# 04_-_3_5_inch.net
KiCad netlist of a schematic drawn in Altium Designer
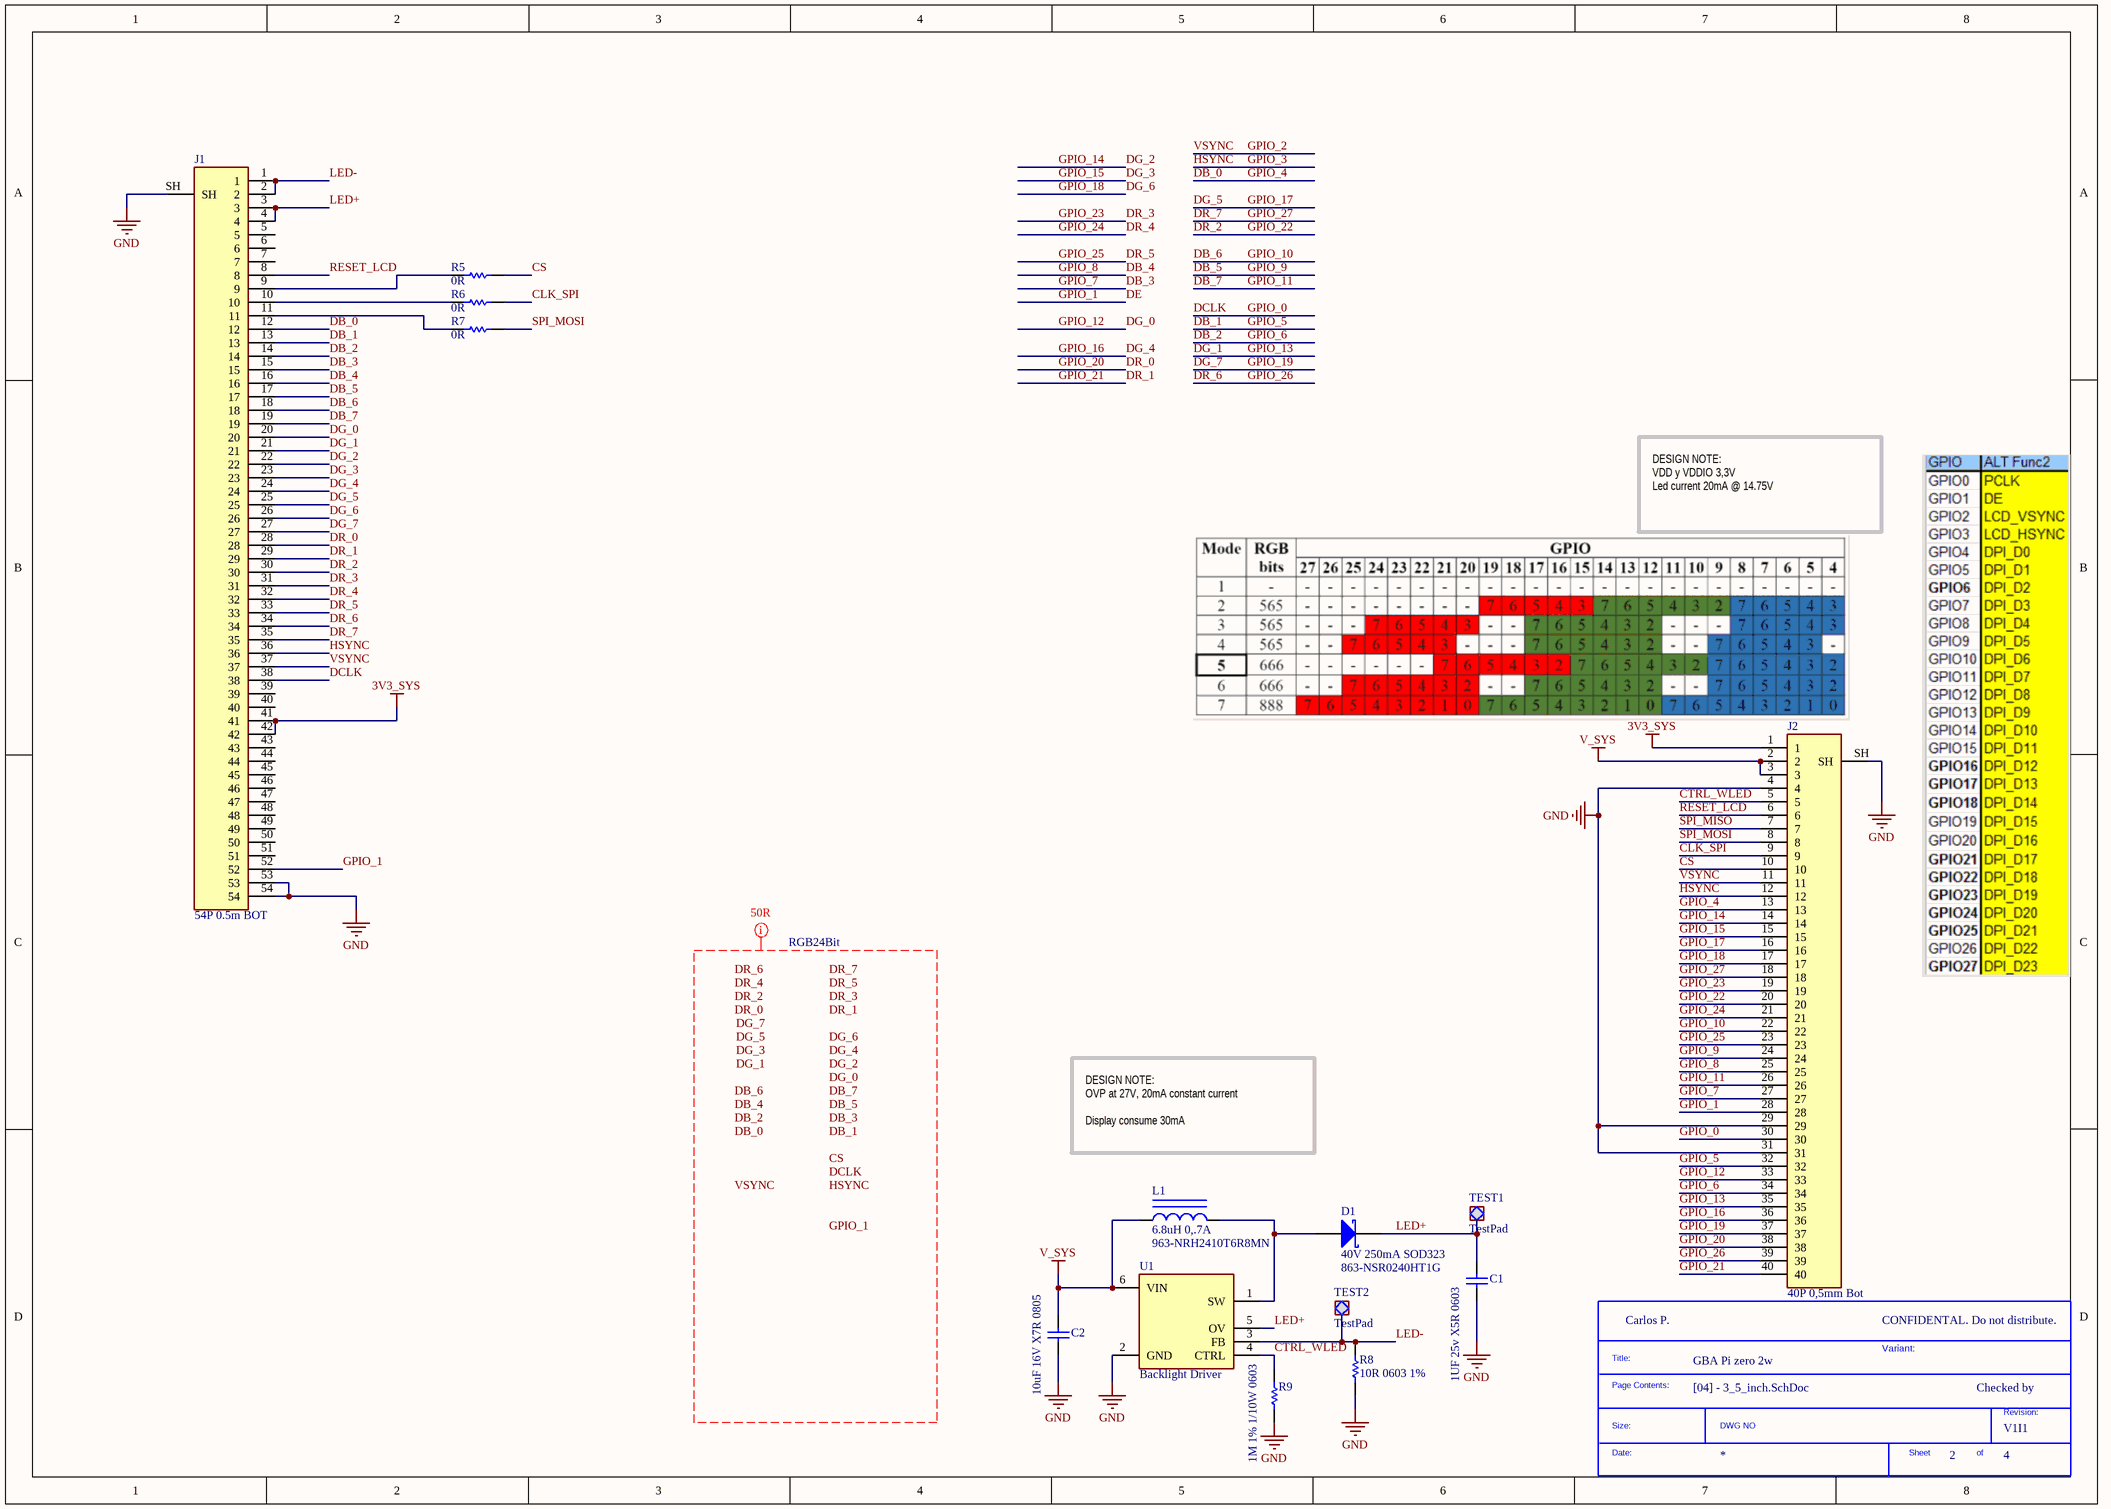
[diagram p0: [04] - 3_5_inch.SchDoc]

(export (version "E")
  (design (tool "Eeschema 10.0.6"))
  (components
    (comp (ref "C1")
      (value "1UF 25v X5R 0603")
      (footprint "C 0603/1608")
      (description "CAP CER 1UF 25V X5R 0603")
      (fields
        (field (name "MANUFACTURER") "Yageo")
        (field (name "MANUFACTURER PART NUMBER") "CC0603KRX5R8BB105")
      )
      (libsource (lib "CM3Board_V1I2") (part "CC0603KRX5R8BB105"))
    )
    (comp (ref "C2")
      (value "10uF 16V X7R 0805")
      (footprint "C 0805/2012")
      (description "CAP CER 10UF 16V X7R 0805")
      (fields
        (field (name "MANUFACTURER") "Samsung Electro-Mechanics")
        (field (name "MANUFACTURER PART NUMBER") "CL21B106KOQNNNE")
      )
      (libsource (lib "CM3Board_V1I2") (part "CL21B106KOQNNNE"))
    )
    (comp (ref "D1")
      (value "40V 250mA SOD323")
      (footprint "SOD-323")
      (description "DIODE SCHOTTKY 40V 250MA SOD323")
      (fields
        (field (name "MANUFACTURER") "ON Semiconductor")
        (field (name "MANUFACTURER PART NUMBER") "NSR0240HT1G")
        (field (name "SUPPLIER PART NUMBER 1") "863-NSR0240HT1G")
      )
      (libsource (lib "DPI_LVDS") (part "NSR0240HT1G"))
    )
    (comp (ref "J1")
      (value "54P 0.5m BOT")
      (footprint "FFC2B35-54-G")
      (description "54W, 0.5MM Ffc Con, R/a, Bottom Con")
      (fields
        (field (name "MANUFACTURER") "Global Connector Technology")
        (field (name "MANUFACTURER PART NUMBER") "FFC2B35-54-G")
      )
      (libsource (lib "GBA") (part "FFC2B35-54-G"))
    )
    (comp (ref "J2")
      (value "40P 0,5mm Bot")
      (footprint "417345920")
      (description "CONN FPC BOTTOM 40POS 0.50MM R/A")
      (fields
        (field (name "MANUFACTURER") "TE Connectivity")
        (field (name "MANUFACTURER PART NUMBER") "4-1734592-0")
      )
      (libsource (lib "GBA") (part "4-1734592-0"))
    )
    (comp (ref "L1")
      (value "6.8uH 0,.7A")
      (footprint "NRH2410T6R8MN")
      (description "Inductor Power Shielded Wirewound 6.8uH 20% 100KHz Ferrite 0.57A 0.492Ohm DCR T/R")
      (fields
        (field (name "MANUFACTURER") "Taiyo Yuden")
        (field (name "MANUFACTURER PART NUMBER") "NRH2410T6R8MN")
        (field (name "SUPPLIER PART NUMBER 1") "963-NRH2410T6R8MN")
      )
      (libsource (lib "GBA") (part "NRH2410T6R8MN"))
    )
    (comp (ref "R5")
      (value "0R")
      (footprint "R 0603/1608")
      (description "RES SMD 0 OHM JUMPER 1/10W 0603")
      (fields
        (field (name "MANUFACTURER") "Yageo")
        (field (name "MANUFACTURER PART NUMBER") "RC0603JR-070RL")
      )
      (libsource (lib "CM3Board_V1I2") (part "RC0603JR-070RL"))
    )
    (comp (ref "R6")
      (value "0R")
      (footprint "R 0603/1608")
      (description "RES SMD 0 OHM JUMPER 1/10W 0603")
      (fields
        (field (name "MANUFACTURER") "Yageo")
        (field (name "MANUFACTURER PART NUMBER") "RC0603JR-070RL")
      )
      (libsource (lib "CM3Board_V1I2") (part "RC0603JR-070RL"))
    )
    (comp (ref "R7")
      (value "0R")
      (footprint "R 0603/1608")
      (description "RES SMD 0 OHM JUMPER 1/10W 0603")
      (fields
        (field (name "MANUFACTURER") "Yageo")
        (field (name "MANUFACTURER PART NUMBER") "RC0603JR-070RL")
      )
      (libsource (lib "CM3Board_V1I2") (part "RC0603JR-070RL"))
    )
    (comp (ref "R8")
      (value "10R 0603 1%")
      (footprint "R 0603/1608")
      (description "High Precision-High Stability Chip Resistor Thin Film 0603 10Ohm 1% Paper T/R")
      (fields
        (field (name "MANUFACTURER") "Yageo")
        (field (name "MANUFACTURER PART NUMBER") "RT0603FRE0710RL")
      )
      (libsource (lib "GBA") (part "RT0603FRE0710RL"))
    )
    (comp (ref "R9")
      (value "1M 1% 1/10W 0603")
      (footprint "R 0603/1608")
      (description "RES SMD 1M OHM 1% 1/10W 0603")
      (fields (field (name "TOLERANCE") "1%"))
      (libsource (lib "CM3Board_V1I2") (part "RC0603FR-071ML"))
    )
    (comp (ref "TEST1")
      (value "TestPad")
      (footprint "TestPad")
      (description "Probe Pad, SMT, ROUND, 2.0MM")
      (libsource (lib "CM3Board") (part "PP_SMT_ROUND_2MM"))
    )
    (comp (ref "TEST2")
      (value "TestPad")
      (footprint "TestPad")
      (description "Probe Pad, SMT, ROUND, 2.0MM")
      (libsource (lib "CM3Board") (part "PP_SMT_ROUND_2MM"))
    )
    (comp (ref "U1")
      (value "Backlight Driver")
      (footprint "SOT95P280X145-6N")
      (description "AP3032 Series 9 V 1.3 MHz Surface Mount White LED Step-Up Converter - SOT-23-6")
      (fields (field (name "MANUFACTURER") "Diodes") (field (name "MANUFACTURER PART NUMBER") "AP3032KTR-G1"))
      (libsource (lib "GBA") (part "AP3032KTR-G1"))
    )
  )
  (nets
    (net (code "1") (name "/CLK_SPI") (class "Default")
      (node (ref "J2") (pin "9") (pinfunction "9_9") (pintype "passive"))
      (node (ref "R6") (pin "2") (pinfunction "2_2") (pintype "passive"))
    )
    (net (code "2") (name "/CS") (class "Default")
      (node (ref "J2") (pin "10") (pinfunction "10_10") (pintype "passive"))
      (node (ref "R5") (pin "2") (pinfunction "2_2") (pintype "passive"))
    )
    (net (code "3") (name "/CTRL_WLED") (class "Default")
      (node (ref "J2") (pin "5") (pinfunction "5_5") (pintype "passive"))
      (node (ref "R9") (pin "2") (pinfunction "2_2") (pintype "passive"))
      (node (ref "U1") (pin "4") (pinfunction "CTRL_4") (pintype "passive"))
    )
    (net (code "4") (name "/DB_0") (class "Default")
      (node (ref "J1") (pin "12") (pinfunction "12_12") (pintype "passive"))
      (node (ref "J2") (pin "13") (pinfunction "13_13") (pintype "passive"))
    )
    (net (code "5") (name "/DB_1") (class "Default")
      (node (ref "J1") (pin "13") (pinfunction "13_13") (pintype "passive"))
      (node (ref "J2") (pin "32") (pinfunction "32_32") (pintype "passive"))
    )
    (net (code "6") (name "/DB_2") (class "Default")
      (node (ref "J1") (pin "14") (pinfunction "14_14") (pintype "passive"))
      (node (ref "J2") (pin "34") (pinfunction "34_34") (pintype "passive"))
    )
    (net (code "7") (name "/DB_3") (class "Default")
      (node (ref "J1") (pin "15") (pinfunction "15_15") (pintype "passive"))
      (node (ref "J2") (pin "27") (pinfunction "27_27") (pintype "passive"))
    )
    (net (code "8") (name "/DB_4") (class "Default")
      (node (ref "J1") (pin "16") (pinfunction "16_16") (pintype "passive"))
      (node (ref "J2") (pin "25") (pinfunction "25_25") (pintype "passive"))
    )
    (net (code "9") (name "/DB_5") (class "Default")
      (node (ref "J1") (pin "17") (pinfunction "17_17") (pintype "passive"))
      (node (ref "J2") (pin "24") (pinfunction "24_24") (pintype "passive"))
    )
    (net (code "10") (name "/DB_6") (class "Default")
      (node (ref "J1") (pin "18") (pinfunction "18_18") (pintype "passive"))
      (node (ref "J2") (pin "22") (pinfunction "22_22") (pintype "passive"))
    )
    (net (code "11") (name "/DB_7") (class "Default")
      (node (ref "J1") (pin "19") (pinfunction "19_19") (pintype "passive"))
      (node (ref "J2") (pin "26") (pinfunction "26_26") (pintype "passive"))
    )
    (net (code "12") (name "/DCLK") (class "Default")
      (node (ref "J1") (pin "38") (pinfunction "38_38") (pintype "passive"))
      (node (ref "J2") (pin "30") (pinfunction "30_30") (pintype "passive"))
    )
    (net (code "13") (name "/DE") (class "Default")
      (node (ref "J1") (pin "52") (pinfunction "52_52") (pintype "passive"))
      (node (ref "J2") (pin "28") (pinfunction "28_28") (pintype "passive"))
    )
    (net (code "14") (name "/DG_0") (class "Default")
      (node (ref "J1") (pin "20") (pinfunction "20_20") (pintype "passive"))
      (node (ref "J2") (pin "33") (pinfunction "33_33") (pintype "passive"))
    )
    (net (code "15") (name "/DG_1") (class "Default")
      (node (ref "J1") (pin "21") (pinfunction "21_21") (pintype "passive"))
      (node (ref "J2") (pin "35") (pinfunction "35_35") (pintype "passive"))
    )
    (net (code "16") (name "/DG_2") (class "Default")
      (node (ref "J1") (pin "22") (pinfunction "22_22") (pintype "passive"))
      (node (ref "J2") (pin "14") (pinfunction "14_14") (pintype "passive"))
    )
    (net (code "17") (name "/DG_3") (class "Default")
      (node (ref "J1") (pin "23") (pinfunction "23_23") (pintype "passive"))
      (node (ref "J2") (pin "15") (pinfunction "15_15") (pintype "passive"))
    )
    (net (code "18") (name "/DG_4") (class "Default")
      (node (ref "J1") (pin "24") (pinfunction "24_24") (pintype "passive"))
      (node (ref "J2") (pin "36") (pinfunction "36_36") (pintype "passive"))
    )
    (net (code "19") (name "/DG_5") (class "Default")
      (node (ref "J1") (pin "25") (pinfunction "25_25") (pintype "passive"))
      (node (ref "J2") (pin "16") (pinfunction "16_16") (pintype "passive"))
    )
    (net (code "20") (name "/DG_6") (class "Default")
      (node (ref "J1") (pin "26") (pinfunction "26_26") (pintype "passive"))
      (node (ref "J2") (pin "17") (pinfunction "17_17") (pintype "passive"))
    )
    (net (code "21") (name "/DG_7") (class "Default")
      (node (ref "J1") (pin "27") (pinfunction "27_27") (pintype "passive"))
      (node (ref "J2") (pin "37") (pinfunction "37_37") (pintype "passive"))
    )
    (net (code "22") (name "/DR_0") (class "Default")
      (node (ref "J1") (pin "28") (pinfunction "28_28") (pintype "passive"))
      (node (ref "J2") (pin "38") (pinfunction "38_38") (pintype "passive"))
    )
    (net (code "23") (name "/DR_1") (class "Default")
      (node (ref "J1") (pin "29") (pinfunction "29_29") (pintype "passive"))
      (node (ref "J2") (pin "40") (pinfunction "40_40") (pintype "passive"))
    )
    (net (code "24") (name "/DR_2") (class "Default")
      (node (ref "J1") (pin "30") (pinfunction "30_30") (pintype "passive"))
      (node (ref "J2") (pin "20") (pinfunction "20_20") (pintype "passive"))
    )
    (net (code "25") (name "/DR_3") (class "Default")
      (node (ref "J1") (pin "31") (pinfunction "31_31") (pintype "passive"))
      (node (ref "J2") (pin "19") (pinfunction "19_19") (pintype "passive"))
    )
    (net (code "26") (name "/DR_4") (class "Default")
      (node (ref "J1") (pin "32") (pinfunction "32_32") (pintype "passive"))
      (node (ref "J2") (pin "21") (pinfunction "21_21") (pintype "passive"))
    )
    (net (code "27") (name "/DR_5") (class "Default")
      (node (ref "J1") (pin "33") (pinfunction "33_33") (pintype "passive"))
      (node (ref "J2") (pin "23") (pinfunction "23_23") (pintype "passive"))
    )
    (net (code "28") (name "/DR_6") (class "Default")
      (node (ref "J1") (pin "34") (pinfunction "34_34") (pintype "passive"))
      (node (ref "J2") (pin "39") (pinfunction "39_39") (pintype "passive"))
    )
    (net (code "29") (name "/DR_7") (class "Default")
      (node (ref "J1") (pin "35") (pinfunction "35_35") (pintype "passive"))
      (node (ref "J2") (pin "18") (pinfunction "18_18") (pintype "passive"))
    )
    (net (code "30") (name "/GPIO_2") (class "Default")
      (node (ref "J1") (pin "37") (pinfunction "37_37") (pintype "passive"))
      (node (ref "J2") (pin "11") (pinfunction "11_11") (pintype "passive"))
    )
    (net (code "31") (name "/GPIO_3") (class "Default")
      (node (ref "J1") (pin "36") (pinfunction "36_36") (pintype "passive"))
      (node (ref "J2") (pin "12") (pinfunction "12_12") (pintype "passive"))
    )
    (net (code "32") (name "/LED+") (class "Default")
      (node (ref "C1") (pin "1") (pinfunction "1_1") (pintype "passive"))
      (node (ref "D1") (pin "1") (pinfunction "K_1") (pintype "passive"))
      (node (ref "J1") (pin "3") (pinfunction "3_3") (pintype "passive"))
      (node (ref "J1") (pin "4") (pinfunction "4_4") (pintype "passive"))
      (node (ref "TEST1") (pin "1") (pinfunction "1_1") (pintype "passive"))
      (node (ref "U1") (pin "5") (pinfunction "OV_5") (pintype "passive"))
    )
    (net (code "33") (name "/LED-") (class "Default")
      (node (ref "J1") (pin "1") (pinfunction "1_1") (pintype "passive"))
      (node (ref "J1") (pin "2") (pinfunction "2_2") (pintype "passive"))
      (node (ref "R8") (pin "2") (pinfunction "2_2") (pintype "passive"))
      (node (ref "TEST2") (pin "1") (pinfunction "1_1") (pintype "passive"))
      (node (ref "U1") (pin "3") (pinfunction "FB_3") (pintype "passive"))
    )
    (net (code "34") (name "/RESET_LCD") (class "Default")
      (node (ref "J1") (pin "8") (pinfunction "8_8") (pintype "passive"))
      (node (ref "J2") (pin "6") (pinfunction "6_6") (pintype "passive"))
    )
    (net (code "35") (name "/SPI_MISO") (class "Default")
      (node (ref "J2") (pin "7") (pinfunction "7_7") (pintype "passive"))
    )
    (net (code "36") (name "/SPI_MOSI") (class "Default")
      (node (ref "J2") (pin "8") (pinfunction "8_8") (pintype "passive"))
      (node (ref "R7") (pin "2") (pinfunction "2_2") (pintype "passive"))
    )
    (net (code "37") (name "3V3_SYS") (class "Default")
      (node (ref "J1") (pin "41") (pinfunction "41_41") (pintype "passive"))
      (node (ref "J1") (pin "42") (pinfunction "42_42") (pintype "passive"))
      (node (ref "J2") (pin "1") (pinfunction "1_1") (pintype "passive"))
    )
    (net (code "38") (name "GND") (class "Default")
      (node (ref "C1") (pin "2") (pinfunction "2_2") (pintype "passive"))
      (node (ref "C2") (pin "1") (pinfunction "1_1") (pintype "passive"))
      (node (ref "J1") (pin "53") (pinfunction "53_53") (pintype "passive"))
      (node (ref "J1") (pin "54") (pinfunction "54_54") (pintype "passive"))
      (node (ref "J1") (pin "SH") (pinfunction "SH_SH") (pintype "passive"))
      (node (ref "J2") (pin "29") (pinfunction "29_29") (pintype "passive"))
      (node (ref "J2") (pin "31") (pinfunction "31_31") (pintype "passive"))
      (node (ref "J2") (pin "4") (pinfunction "4_4") (pintype "passive"))
      (node (ref "J2") (pin "SH") (pinfunction "SH_SH") (pintype "passive"))
      (node (ref "R8") (pin "1") (pinfunction "1_1") (pintype "passive"))
      (node (ref "R9") (pin "1") (pinfunction "1_1") (pintype "passive"))
      (node (ref "U1") (pin "2") (pinfunction "GND_2") (pintype "passive"))
    )
    (net (code "39") (name "Net-(D1-A)") (class "Default")
      (node (ref "D1") (pin "2") (pinfunction "A_2") (pintype "passive"))
      (node (ref "L1") (pin "2") (pinfunction "2_2") (pintype "passive"))
      (node (ref "U1") (pin "1") (pinfunction "SW_1") (pintype "passive"))
    )
    (net (code "40") (name "Net-(J1-Pad9)") (class "Default")
      (node (ref "J1") (pin "9") (pinfunction "9_9") (pintype "passive"))
      (node (ref "R5") (pin "1") (pinfunction "1_1") (pintype "passive"))
    )
    (net (code "41") (name "Net-(J1-Pad10)") (class "Default")
      (node (ref "J1") (pin "10") (pinfunction "10_10") (pintype "passive"))
      (node (ref "R6") (pin "1") (pinfunction "1_1") (pintype "passive"))
    )
    (net (code "42") (name "Net-(J1-Pad11)") (class "Default")
      (node (ref "J1") (pin "11") (pinfunction "11_11") (pintype "passive"))
      (node (ref "R7") (pin "1") (pinfunction "1_1") (pintype "passive"))
    )
    (net (code "43") (name "V_SYS") (class "Default")
      (node (ref "C2") (pin "2") (pinfunction "2_2") (pintype "passive"))
      (node (ref "J2") (pin "2") (pinfunction "2_2") (pintype "passive"))
      (node (ref "J2") (pin "3") (pinfunction "3_3") (pintype "passive"))
      (node (ref "L1") (pin "1") (pinfunction "1_1") (pintype "passive"))
      (node (ref "U1") (pin "6") (pinfunction "VIN_6") (pintype "passive"))
    )
    (net (code "44") (name "unconnected-(J1-Pad5)") (class "Default")
      (node (ref "J1") (pin "5") (pinfunction "5_5") (pintype "passive"))
    )
    (net (code "45") (name "unconnected-(J1-Pad6)") (class "Default")
      (node (ref "J1") (pin "6") (pinfunction "6_6") (pintype "passive"))
    )
    (net (code "46") (name "unconnected-(J1-Pad7)") (class "Default")
      (node (ref "J1") (pin "7") (pinfunction "7_7") (pintype "passive"))
    )
    (net (code "47") (name "unconnected-(J1-Pad39)") (class "Default")
      (node (ref "J1") (pin "39") (pinfunction "39_39") (pintype "passive"))
    )
    (net (code "48") (name "unconnected-(J1-Pad40)") (class "Default")
      (node (ref "J1") (pin "40") (pinfunction "40_40") (pintype "passive"))
    )
    (net (code "49") (name "unconnected-(J1-Pad43)") (class "Default")
      (node (ref "J1") (pin "43") (pinfunction "43_43") (pintype "passive"))
    )
    (net (code "50") (name "unconnected-(J1-Pad44)") (class "Default")
      (node (ref "J1") (pin "44") (pinfunction "44_44") (pintype "passive"))
    )
    (net (code "51") (name "unconnected-(J1-Pad45)") (class "Default")
      (node (ref "J1") (pin "45") (pinfunction "45_45") (pintype "passive"))
    )
    (net (code "52") (name "unconnected-(J1-Pad46)") (class "Default")
      (node (ref "J1") (pin "46") (pinfunction "46_46") (pintype "passive"))
    )
    (net (code "53") (name "unconnected-(J1-Pad47)") (class "Default")
      (node (ref "J1") (pin "47") (pinfunction "47_47") (pintype "passive"))
    )
    (net (code "54") (name "unconnected-(J1-Pad48)") (class "Default")
      (node (ref "J1") (pin "48") (pinfunction "48_48") (pintype "passive"))
    )
    (net (code "55") (name "unconnected-(J1-Pad49)") (class "Default")
      (node (ref "J1") (pin "49") (pinfunction "49_49") (pintype "passive"))
    )
    (net (code "56") (name "unconnected-(J1-Pad50)") (class "Default")
      (node (ref "J1") (pin "50") (pinfunction "50_50") (pintype "passive"))
    )
    (net (code "57") (name "unconnected-(J1-Pad51)") (class "Default")
      (node (ref "J1") (pin "51") (pinfunction "51_51") (pintype "passive"))
    )
  )
)
